# Analog_Electronics_Fundamentals_103_-_La.net
KiCad netlist of a schematic drawn in EAGLE
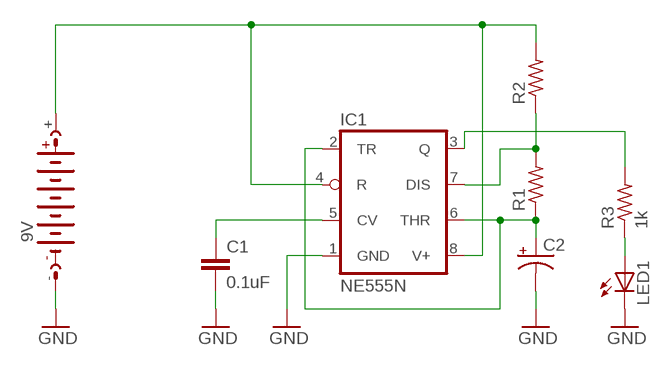
[diagram p0: schematic, sheet 1]

(export (version "E")
  (design (tool "Eeschema 10.0.6"))
  (components
    (comp (ref "9V")
      (value "AB9V")
      (footprint "eagle-import:AB9V")
      (libsource (lib "eagle-import") (part "AB9V"))
    )
    (comp (ref "C1")
      (value "0.1uF")
      (footprint "eagle-import:C025-024X044")
      (libsource (lib "eagle-import") (part "C-EU025-024X044"))
    )
    (comp (ref "C2")
      (value "CPOL-USTT5D11")
      (footprint "eagle-import:TT5D11")
      (libsource (lib "eagle-import") (part "CPOL-USTT5D11"))
    )
    (comp (ref "IC1")
      (value "NE555N")
      (footprint "eagle-import:DIL08")
      (libsource (lib "eagle-import") (part "555NNE"))
    )
    (comp (ref "LED1")
      (value "LED5MM")
      (footprint "eagle-import:LED5MM")
      (libsource (lib "eagle-import") (part "LED5MM"))
    )
    (comp (ref "R1")
      (value "R-US_0204/7")
      (footprint "eagle-import:0204_7")
      (libsource (lib "eagle-import") (part "R-US_0204/7"))
    )
    (comp (ref "R2")
      (value "R-US_0204/7")
      (footprint "eagle-import:0204_7")
      (libsource (lib "eagle-import") (part "R-US_0204/7"))
    )
    (comp (ref "R3")
      (value "1k")
      (footprint "eagle-import:0204_7")
      (libsource (lib "eagle-import") (part "R-US_0204/7"))
    )
  )
  (nets
    (net (code "1") (name "GND") (class "Default")
      (node (ref "9V") (pin "-") (pinfunction "-_-") (pintype "passive"))
      (node (ref "C1") (pin "2") (pinfunction "2_2") (pintype "passive"))
      (node (ref "C2") (pin "-") (pinfunction "-_-") (pintype "passive"))
      (node (ref "IC1") (pin "1") (pinfunction "GND_1") (pintype "power_in"))
      (node (ref "LED1") (pin "K") (pinfunction "C_K") (pintype "passive"))
    )
    (net (code "2") (name "Net-(IC1-CV)") (class "Default")
      (node (ref "C1") (pin "1") (pinfunction "1_1") (pintype "passive"))
      (node (ref "IC1") (pin "5") (pinfunction "CV_5") (pintype "input"))
    )
    (net (code "3") (name "Net-(IC1-DIS)") (class "Default")
      (node (ref "IC1") (pin "7") (pinfunction "DIS_7") (pintype "input"))
      (node (ref "R1") (pin "2") (pinfunction "2_2") (pintype "passive"))
      (node (ref "R2") (pin "1") (pinfunction "1_1") (pintype "passive"))
    )
    (net (code "4") (name "Net-(IC1-Q)") (class "Default")
      (node (ref "IC1") (pin "3") (pinfunction "Q_3") (pintype "output"))
      (node (ref "R3") (pin "2") (pinfunction "2_2") (pintype "passive"))
    )
    (net (code "5") (name "Net-(IC1-R)") (class "Default")
      (node (ref "9V") (pin "+") (pinfunction "+_+") (pintype "passive"))
      (node (ref "IC1") (pin "4") (pinfunction "R_4") (pintype "input"))
      (node (ref "IC1") (pin "8") (pinfunction "V+_8") (pintype "power_in"))
      (node (ref "R2") (pin "2") (pinfunction "2_2") (pintype "passive"))
    )
    (net (code "6") (name "Net-(IC1-THR)") (class "Default")
      (node (ref "C2") (pin "+") (pinfunction "+_+") (pintype "passive"))
      (node (ref "IC1") (pin "2") (pinfunction "TR_2") (pintype "input"))
      (node (ref "IC1") (pin "6") (pinfunction "THR_6") (pintype "input"))
      (node (ref "R1") (pin "1") (pinfunction "1_1") (pintype "passive"))
    )
    (net (code "7") (name "Net-(LED1-PadA)") (class "Default")
      (node (ref "LED1") (pin "A") (pinfunction "A_A") (pintype "passive"))
      (node (ref "R3") (pin "1") (pinfunction "1_1") (pintype "passive"))
    )
  )
)
